# Matrix_Module.net
KiCad netlist of a schematic drawn in EAGLE
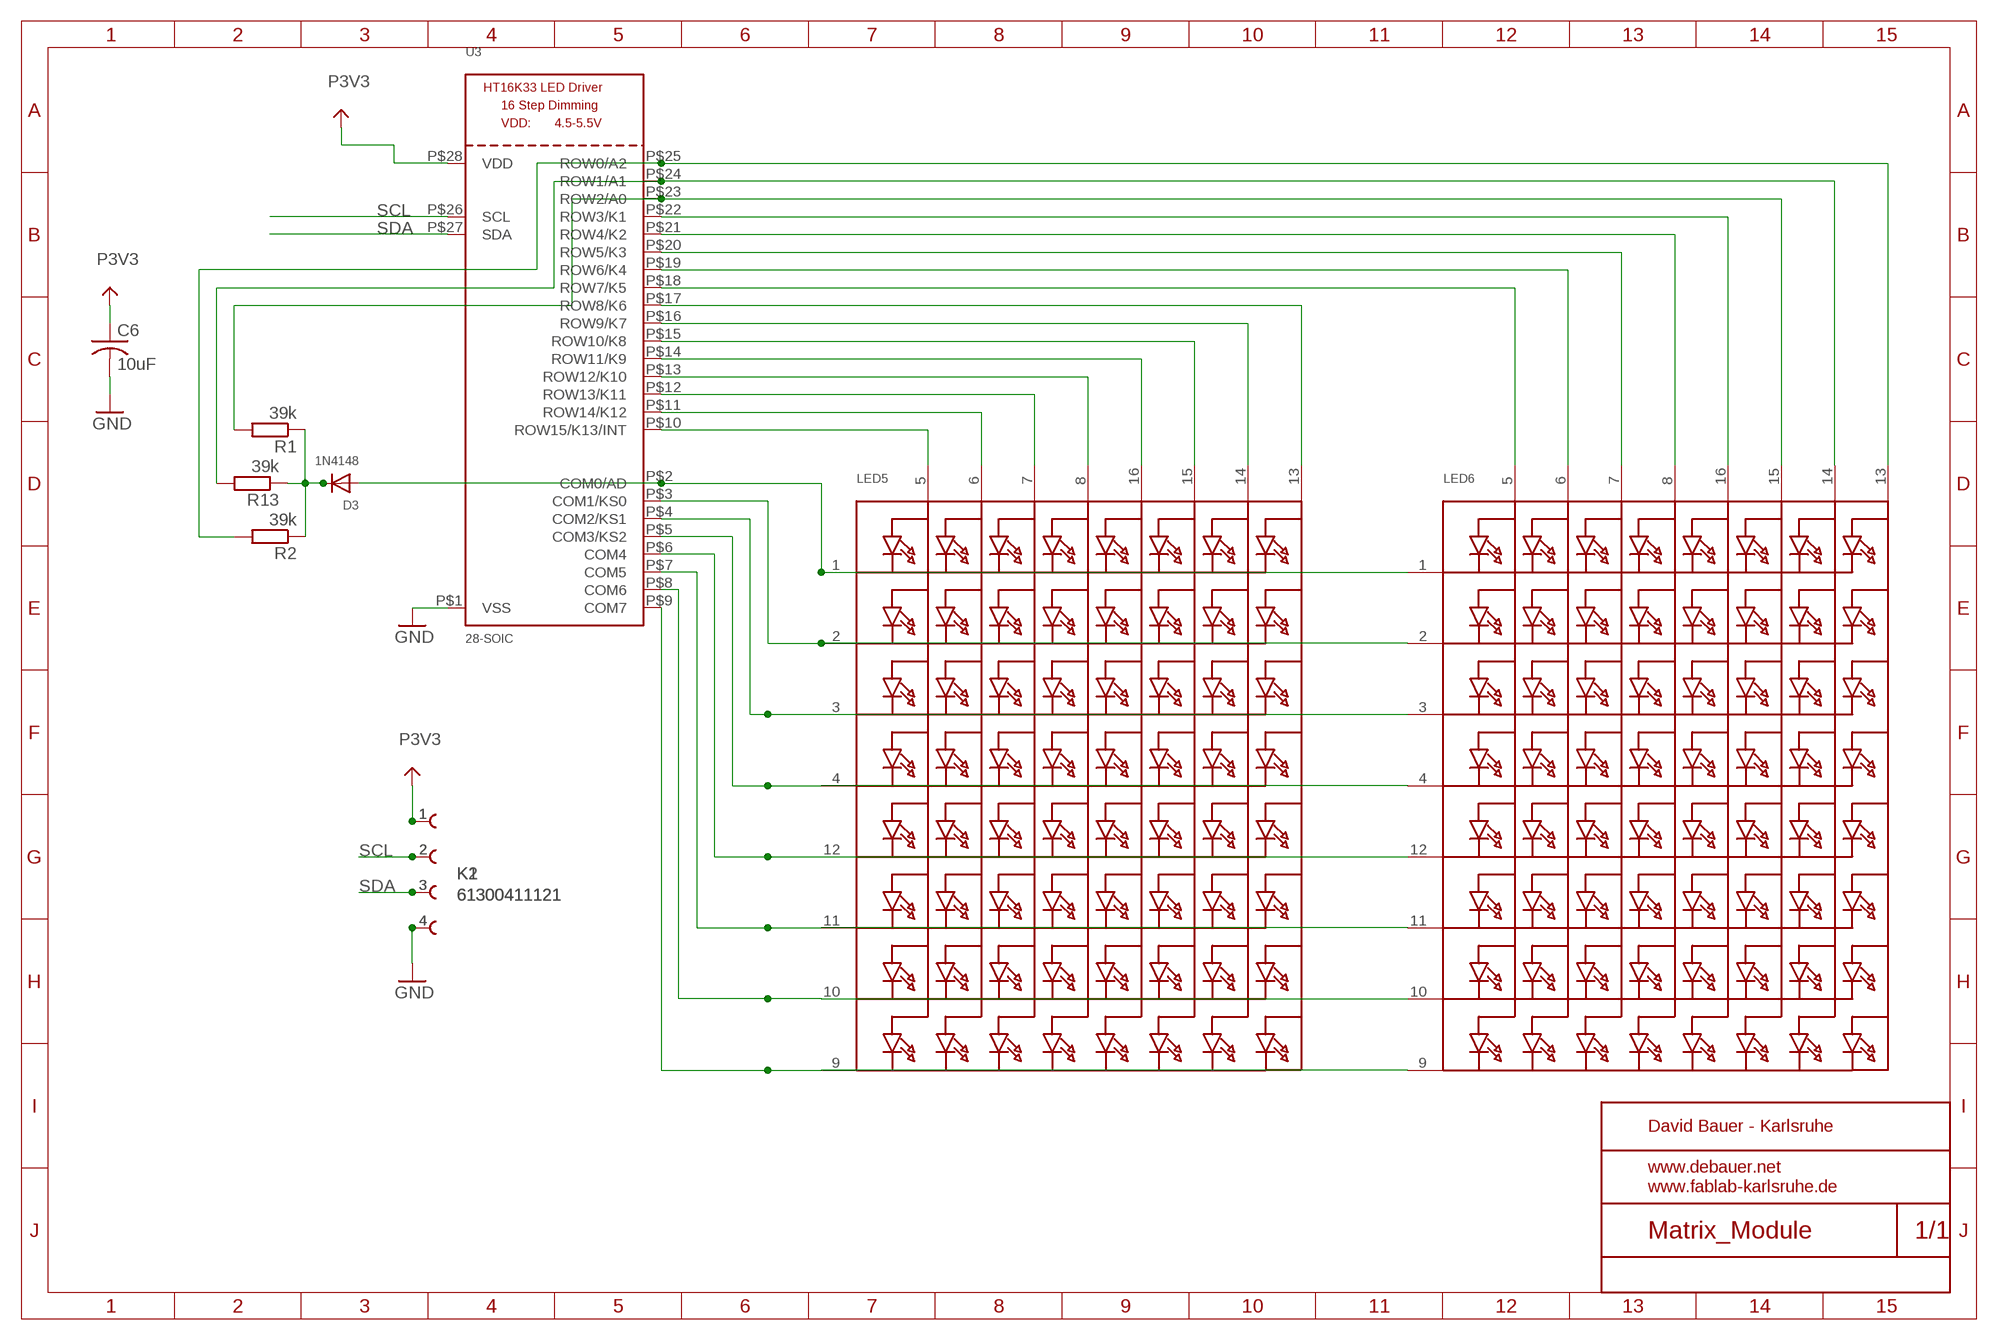
[diagram p0: schematic, sheet 1]

(export (version "E")
  (design (tool "Eeschema 10.0.6"))
  (components
    (comp (ref "C6")
      (value "10uF")
      (footprint "eagle-import:C0805")
      (libsource (lib "eagle-import") (part "C-USC0805"))
    )
    (comp (ref "D3")
      (value "1N4148")
      (footprint "eagle-import:SOD-323F")
      (libsource (lib "eagle-import") (part "DIODESOD-323F"))
    )
    (comp (ref "K1")
      (value "61300411121")
      (footprint "eagle-import:61300411121")
      (libsource (lib "eagle-import") (part "61300411121"))
    )
    (comp (ref "K2")
      (value "61300411121")
      (footprint "eagle-import:61300411121")
      (libsource (lib "eagle-import") (part "61300411121"))
    )
    (comp (ref "LED5")
      (value "SEGMENT_8X8_ROWCATHODE")
      (footprint "eagle-import:SEGMENT_BL-M07C881UR")
      (libsource (lib "eagle-import") (part "SEGMENT_8X8_ROWCATHODE"))
    )
    (comp (ref "LED6")
      (value "SEGMENT_8X8_ROWCATHODE")
      (footprint "eagle-import:SEGMENT_BL-M07C881UR")
      (libsource (lib "eagle-import") (part "SEGMENT_8X8_ROWCATHODE"))
    )
    (comp (ref "R1")
      (value "39k")
      (footprint "eagle-import:R0805")
      (libsource (lib "eagle-import") (part "R-EU_R0805"))
    )
    (comp (ref "R2")
      (value "39k")
      (footprint "eagle-import:R0805")
      (libsource (lib "eagle-import") (part "R-EU_R0805"))
    )
    (comp (ref "R13")
      (value "39k")
      (footprint "eagle-import:R0805")
      (libsource (lib "eagle-import") (part "R-EU_R0805"))
    )
    (comp (ref "U3")
      (value "28-SOIC")
      (footprint "eagle-import:SOP28_300MIL")
      (libsource (lib "eagle-import") (part "HT16K33_SOP28"))
    )
  )
  (nets
    (net (code "1") (name "/SCL") (class "Default")
      (node (ref "K1") (pin "2") (pinfunction "2_2") (pintype "passive"))
      (node (ref "K2") (pin "2") (pinfunction "2_2") (pintype "passive"))
      (node (ref "U3") (pin "P$26") (pinfunction "SCL_P$26") (pintype "bidirectional"))
    )
    (net (code "2") (name "/SDA") (class "Default")
      (node (ref "K1") (pin "3") (pinfunction "3_3") (pintype "passive"))
      (node (ref "K2") (pin "3") (pinfunction "3_3") (pintype "passive"))
      (node (ref "U3") (pin "P$27") (pinfunction "SDA_P$27") (pintype "bidirectional"))
    )
    (net (code "3") (name "GND") (class "Default")
      (node (ref "C6") (pin "2") (pinfunction "2_2") (pintype "passive"))
      (node (ref "K1") (pin "4") (pinfunction "4_4") (pintype "passive"))
      (node (ref "K2") (pin "4") (pinfunction "4_4") (pintype "passive"))
      (node (ref "U3") (pin "P$1") (pinfunction "VSS_P$1") (pintype "bidirectional"))
    )
    (net (code "4") (name "Net-(D3-PadC)") (class "Default")
      (node (ref "D3") (pin "C") (pinfunction "C_C") (pintype "passive"))
      (node (ref "R1") (pin "1") (pinfunction "1_1") (pintype "passive"))
      (node (ref "R13") (pin "1") (pinfunction "1_1") (pintype "passive"))
      (node (ref "R2") (pin "1") (pinfunction "1_1") (pintype "passive"))
    )
    (net (code "5") (name "Net-(LED5-A1)") (class "Default")
      (node (ref "LED5") (pin "5") (pinfunction "A1_5") (pintype "bidirectional"))
      (node (ref "U3") (pin "P$10") (pinfunction "ROW15/K13/INT_P$10") (pintype "bidirectional"))
    )
    (net (code "6") (name "Net-(LED5-A2)") (class "Default")
      (node (ref "LED5") (pin "6") (pinfunction "A2_6") (pintype "bidirectional"))
      (node (ref "U3") (pin "P$11") (pinfunction "ROW14/K12_P$11") (pintype "bidirectional"))
    )
    (net (code "7") (name "Net-(LED5-A3)") (class "Default")
      (node (ref "LED5") (pin "7") (pinfunction "A3_7") (pintype "bidirectional"))
      (node (ref "U3") (pin "P$12") (pinfunction "ROW13/K11_P$12") (pintype "bidirectional"))
    )
    (net (code "8") (name "Net-(LED5-A4)") (class "Default")
      (node (ref "LED5") (pin "8") (pinfunction "A4_8") (pintype "bidirectional"))
      (node (ref "U3") (pin "P$13") (pinfunction "ROW12/K10_P$13") (pintype "bidirectional"))
    )
    (net (code "9") (name "Net-(LED5-A5)") (class "Default")
      (node (ref "LED5") (pin "16") (pinfunction "A5_16") (pintype "bidirectional"))
      (node (ref "U3") (pin "P$14") (pinfunction "ROW11/K9_P$14") (pintype "bidirectional"))
    )
    (net (code "10") (name "Net-(LED5-A6)") (class "Default")
      (node (ref "LED5") (pin "15") (pinfunction "A6_15") (pintype "bidirectional"))
      (node (ref "U3") (pin "P$15") (pinfunction "ROW10/K8_P$15") (pintype "bidirectional"))
    )
    (net (code "11") (name "Net-(LED5-A7)") (class "Default")
      (node (ref "LED5") (pin "14") (pinfunction "A7_14") (pintype "bidirectional"))
      (node (ref "U3") (pin "P$16") (pinfunction "ROW9/K7_P$16") (pintype "bidirectional"))
    )
    (net (code "12") (name "Net-(LED5-A8)") (class "Default")
      (node (ref "LED5") (pin "13") (pinfunction "A8_13") (pintype "bidirectional"))
      (node (ref "U3") (pin "P$17") (pinfunction "ROW8/K6_P$17") (pintype "bidirectional"))
    )
    (net (code "13") (name "Net-(LED5-K1)") (class "Default")
      (node (ref "D3") (pin "A") (pinfunction "A_A") (pintype "passive"))
      (node (ref "LED5") (pin "1") (pinfunction "K1_1") (pintype "bidirectional"))
      (node (ref "LED6") (pin "1") (pinfunction "K1_1") (pintype "bidirectional"))
      (node (ref "U3") (pin "P$2") (pinfunction "COM0/AD_P$2") (pintype "bidirectional"))
    )
    (net (code "14") (name "Net-(LED5-K2)") (class "Default")
      (node (ref "LED5") (pin "2") (pinfunction "K2_2") (pintype "bidirectional"))
      (node (ref "LED6") (pin "2") (pinfunction "K2_2") (pintype "bidirectional"))
      (node (ref "U3") (pin "P$3") (pinfunction "COM1/KS0_P$3") (pintype "bidirectional"))
    )
    (net (code "15") (name "Net-(LED5-K3)") (class "Default")
      (node (ref "LED5") (pin "3") (pinfunction "K3_3") (pintype "bidirectional"))
      (node (ref "LED6") (pin "3") (pinfunction "K3_3") (pintype "bidirectional"))
      (node (ref "U3") (pin "P$4") (pinfunction "COM2/KS1_P$4") (pintype "bidirectional"))
    )
    (net (code "16") (name "Net-(LED5-K4)") (class "Default")
      (node (ref "LED5") (pin "4") (pinfunction "K4_4") (pintype "bidirectional"))
      (node (ref "LED6") (pin "4") (pinfunction "K4_4") (pintype "bidirectional"))
      (node (ref "U3") (pin "P$5") (pinfunction "COM3/KS2_P$5") (pintype "bidirectional"))
    )
    (net (code "17") (name "Net-(LED5-K5)") (class "Default")
      (node (ref "LED5") (pin "12") (pinfunction "K5_12") (pintype "bidirectional"))
      (node (ref "LED6") (pin "12") (pinfunction "K5_12") (pintype "bidirectional"))
      (node (ref "U3") (pin "P$6") (pinfunction "COM4_P$6") (pintype "bidirectional"))
    )
    (net (code "18") (name "Net-(LED5-K6)") (class "Default")
      (node (ref "LED5") (pin "11") (pinfunction "K6_11") (pintype "bidirectional"))
      (node (ref "LED6") (pin "11") (pinfunction "K6_11") (pintype "bidirectional"))
      (node (ref "U3") (pin "P$7") (pinfunction "COM5_P$7") (pintype "bidirectional"))
    )
    (net (code "19") (name "Net-(LED5-K7)") (class "Default")
      (node (ref "LED5") (pin "10") (pinfunction "K7_10") (pintype "bidirectional"))
      (node (ref "LED6") (pin "10") (pinfunction "K7_10") (pintype "bidirectional"))
      (node (ref "U3") (pin "P$8") (pinfunction "COM6_P$8") (pintype "bidirectional"))
    )
    (net (code "20") (name "Net-(LED5-K8)") (class "Default")
      (node (ref "LED5") (pin "9") (pinfunction "K8_9") (pintype "bidirectional"))
      (node (ref "LED6") (pin "9") (pinfunction "K8_9") (pintype "bidirectional"))
      (node (ref "U3") (pin "P$9") (pinfunction "COM7_P$9") (pintype "bidirectional"))
    )
    (net (code "21") (name "Net-(LED6-A1)") (class "Default")
      (node (ref "LED6") (pin "5") (pinfunction "A1_5") (pintype "bidirectional"))
      (node (ref "U3") (pin "P$18") (pinfunction "ROW7/K5_P$18") (pintype "bidirectional"))
    )
    (net (code "22") (name "Net-(LED6-A2)") (class "Default")
      (node (ref "LED6") (pin "6") (pinfunction "A2_6") (pintype "bidirectional"))
      (node (ref "U3") (pin "P$19") (pinfunction "ROW6/K4_P$19") (pintype "bidirectional"))
    )
    (net (code "23") (name "Net-(LED6-A3)") (class "Default")
      (node (ref "LED6") (pin "7") (pinfunction "A3_7") (pintype "bidirectional"))
      (node (ref "U3") (pin "P$20") (pinfunction "ROW5/K3_P$20") (pintype "bidirectional"))
    )
    (net (code "24") (name "Net-(LED6-A4)") (class "Default")
      (node (ref "LED6") (pin "8") (pinfunction "A4_8") (pintype "bidirectional"))
      (node (ref "U3") (pin "P$21") (pinfunction "ROW4/K2_P$21") (pintype "bidirectional"))
    )
    (net (code "25") (name "Net-(LED6-A5)") (class "Default")
      (node (ref "LED6") (pin "16") (pinfunction "A5_16") (pintype "bidirectional"))
      (node (ref "U3") (pin "P$22") (pinfunction "ROW3/K1_P$22") (pintype "bidirectional"))
    )
    (net (code "26") (name "Net-(LED6-A6)") (class "Default")
      (node (ref "LED6") (pin "15") (pinfunction "A6_15") (pintype "bidirectional"))
      (node (ref "R1") (pin "2") (pinfunction "2_2") (pintype "passive"))
      (node (ref "U3") (pin "P$23") (pinfunction "ROW2/A0_P$23") (pintype "bidirectional"))
    )
    (net (code "27") (name "Net-(LED6-A7)") (class "Default")
      (node (ref "LED6") (pin "14") (pinfunction "A7_14") (pintype "bidirectional"))
      (node (ref "R13") (pin "2") (pinfunction "2_2") (pintype "passive"))
      (node (ref "U3") (pin "P$24") (pinfunction "ROW1/A1_P$24") (pintype "bidirectional"))
    )
    (net (code "28") (name "Net-(LED6-A8)") (class "Default")
      (node (ref "LED6") (pin "13") (pinfunction "A8_13") (pintype "bidirectional"))
      (node (ref "R2") (pin "2") (pinfunction "2_2") (pintype "passive"))
      (node (ref "U3") (pin "P$25") (pinfunction "ROW0/A2_P$25") (pintype "bidirectional"))
    )
    (net (code "29") (name "P3V3") (class "Default")
      (node (ref "C6") (pin "1") (pinfunction "1_1") (pintype "passive"))
      (node (ref "K1") (pin "1") (pinfunction "1_1") (pintype "passive"))
      (node (ref "K2") (pin "1") (pinfunction "1_1") (pintype "passive"))
      (node (ref "U3") (pin "P$28") (pinfunction "VDD_P$28") (pintype "bidirectional"))
    )
  )
)
